# Serial_Board_Overview.net
KiCad netlist of a schematic drawn in Altium Designer
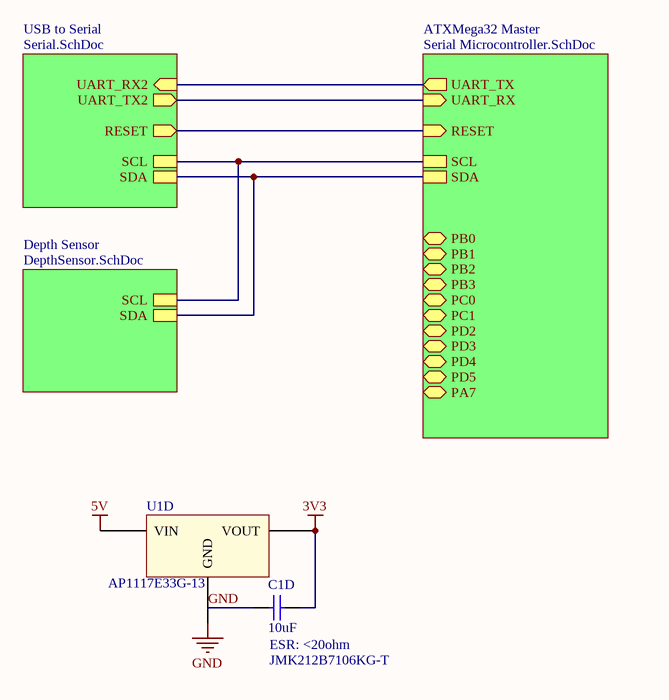
[diagram p0: Serial Board Overview.SchDoc]

(export (version "E")
  (design (tool "Eeschema 10.0.6"))
  (components
    (comp (ref "C1D")
      (value "10uF")
      (footprint "C0805")
      (description "Unpolarized Capacitor")
      (fields
        (field (name "ESR") "<20ohm")
        (field (name "MANUFACTURER PART NUMBER") "JMK212B7106KG-T")
        (field (name "Comment") ".1uF")
      )
      (libsource (lib "URC_Lib") (part "Cap"))
    )
    (comp (ref "U1D")
      (value "AP1117E33G-13")
      (footprint "AP1117")
      (description "3.3V 1A Linear Regulator")
      (fields (field (name "MANUFACTURER PART NUMBER") "AP1117E33G-13"))
      (libsource (lib "URC") (part "AP1117E33G-13"))
    )
  )
  (nets
    (net (code "17") (name "3V3") (class "Default")
      (node (ref "C1D") (pin "1") (pinfunction "1_1") (pintype "passive"))
      (node (ref "U1D") (pin "VOUT") (pinfunction "VOUT_VOUT") (pintype "passive"))
    )
    (net (code "18") (name "5V") (class "Default")
      (node (ref "U1D") (pin "VIN") (pinfunction "VIN_VIN") (pintype "passive"))
    )
    (net (code "19") (name "GND") (class "Default")
      (node (ref "C1D") (pin "2") (pinfunction "2_2") (pintype "passive"))
      (node (ref "U1D") (pin "GND") (pinfunction "GND_GND") (pintype "passive"))
    )
  )
)
